# laser_show_adc_uart.net
KiCad netlist of a schematic drawn in Altium Designer
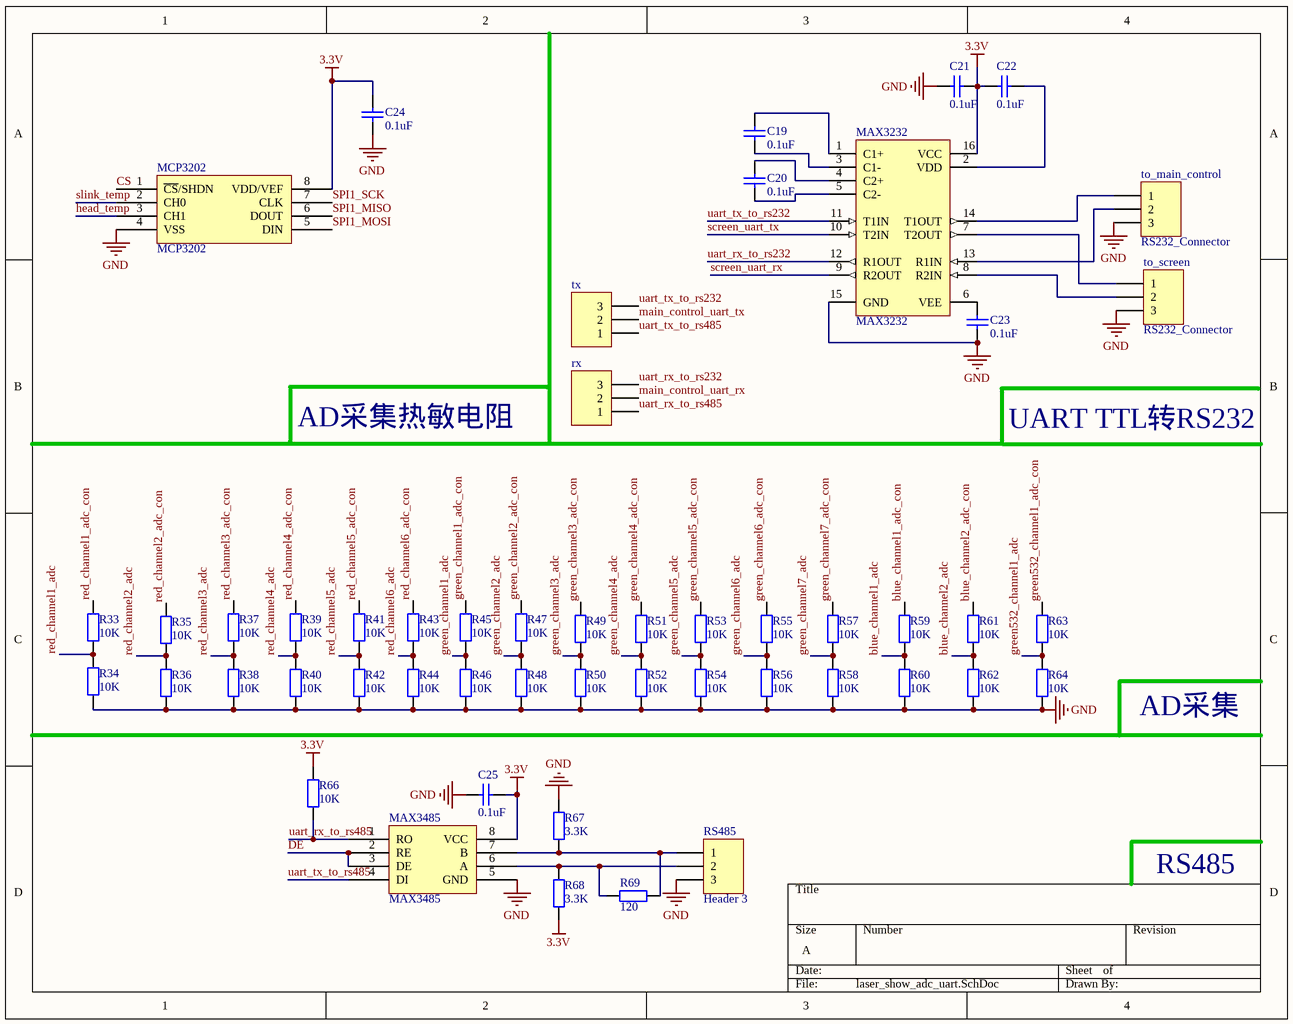
[diagram p0: laser_show_adc_uart.SchDoc]

(export (version "E")
  (design (tool "Eeschema 10.0.6"))
  (components
    (comp (ref "C19")
      (value "0.1uF")
      (footprint "0603C")
      (description "capacitance")
      (libsource (lib "RobotSCHLibrary") (part "CAP"))
    )
    (comp (ref "C20")
      (value "0.1uF")
      (footprint "0603C")
      (description "capacitance")
      (libsource (lib "RobotSCHLibrary") (part "CAP"))
    )
    (comp (ref "C21")
      (value "0.1uF")
      (footprint "0603C")
      (description "capacitance")
      (libsource (lib "RobotSCHLibrary") (part "CAP"))
    )
    (comp (ref "C22")
      (value "0.1uF")
      (footprint "0603C")
      (description "capacitance")
      (libsource (lib "RobotSCHLibrary") (part "CAP"))
    )
    (comp (ref "C23")
      (value "0.1uF")
      (footprint "0603C")
      (description "capacitance")
      (libsource (lib "RobotSCHLibrary") (part "CAP"))
    )
    (comp (ref "C24")
      (value "0.1uF")
      (footprint "0603C")
      (description "capacitance")
      (libsource (lib "RobotSCHLibrary") (part "CAP"))
    )
    (comp (ref "C25")
      (value "0.1uF")
      (footprint "0603C")
      (description "capacitance")
      (libsource (lib "RobotSCHLibrary") (part "CAP"))
    )
    (comp (ref "MAX3232")
      (value "MAX3232")
      (footprint "SO-16")
      (description "+5V Powered, Multi-Channel RS-232 Driver/Receiver")
      (fields (field (name "PUBLISHER") "Altium Limited"))
      (libsource (lib "Fszhang") (part "MAX232"))
    )
    (comp (ref "MAX3485")
      (value "MAX3485")
      (footprint "so-8")
      (libsource (lib "RobotSCHLibrary") (part "MAX485"))
    )
    (comp (ref "MCP3202")
      (value "MCP3202")
      (footprint "SOIC8N_L")
      (libsource (lib "RobotSCHLibrary") (part "MCP3202"))
    )
    (comp (ref "R33")
      (value "10K")
      (footprint "0805R")
      (description "resistor")
      (libsource (lib "RobotSCHLibrary") (part "RES"))
    )
    (comp (ref "R34")
      (value "10K")
      (footprint "0805R")
      (description "resistor")
      (libsource (lib "RobotSCHLibrary") (part "RES"))
    )
    (comp (ref "R35")
      (value "10K")
      (footprint "0805R")
      (description "resistor")
      (libsource (lib "RobotSCHLibrary") (part "RES"))
    )
    (comp (ref "R36")
      (value "10K")
      (footprint "0805R")
      (description "resistor")
      (libsource (lib "RobotSCHLibrary") (part "RES"))
    )
    (comp (ref "R37")
      (value "10K")
      (footprint "0805R")
      (description "resistor")
      (libsource (lib "RobotSCHLibrary") (part "RES"))
    )
    (comp (ref "R38")
      (value "10K")
      (footprint "0805R")
      (description "resistor")
      (libsource (lib "RobotSCHLibrary") (part "RES"))
    )
    (comp (ref "R39")
      (value "10K")
      (footprint "0805R")
      (description "resistor")
      (libsource (lib "RobotSCHLibrary") (part "RES"))
    )
    (comp (ref "R40")
      (value "10K")
      (footprint "0805R")
      (description "resistor")
      (libsource (lib "RobotSCHLibrary") (part "RES"))
    )
    (comp (ref "R41")
      (value "10K")
      (footprint "0805R")
      (description "resistor")
      (libsource (lib "RobotSCHLibrary") (part "RES"))
    )
    (comp (ref "R42")
      (value "10K")
      (footprint "0805R")
      (description "resistor")
      (libsource (lib "RobotSCHLibrary") (part "RES"))
    )
    (comp (ref "R43")
      (value "10K")
      (footprint "0805R")
      (description "resistor")
      (libsource (lib "RobotSCHLibrary") (part "RES"))
    )
    (comp (ref "R44")
      (value "10K")
      (footprint "0805R")
      (description "resistor")
      (libsource (lib "RobotSCHLibrary") (part "RES"))
    )
    (comp (ref "R45")
      (value "10K")
      (footprint "0805R")
      (description "resistor")
      (libsource (lib "RobotSCHLibrary") (part "RES"))
    )
    (comp (ref "R46")
      (value "10K")
      (footprint "0805R")
      (description "resistor")
      (libsource (lib "RobotSCHLibrary") (part "RES"))
    )
    (comp (ref "R47")
      (value "10K")
      (footprint "0805R")
      (description "resistor")
      (libsource (lib "RobotSCHLibrary") (part "RES"))
    )
    (comp (ref "R48")
      (value "10K")
      (footprint "0805R")
      (description "resistor")
      (libsource (lib "RobotSCHLibrary") (part "RES"))
    )
    (comp (ref "R49")
      (value "10K")
      (footprint "0805R")
      (description "resistor")
      (libsource (lib "RobotSCHLibrary") (part "RES"))
    )
    (comp (ref "R50")
      (value "10K")
      (footprint "0805R")
      (description "resistor")
      (libsource (lib "RobotSCHLibrary") (part "RES"))
    )
    (comp (ref "R51")
      (value "10K")
      (footprint "0805R")
      (description "resistor")
      (libsource (lib "RobotSCHLibrary") (part "RES"))
    )
    (comp (ref "R52")
      (value "10K")
      (footprint "0805R")
      (description "resistor")
      (libsource (lib "RobotSCHLibrary") (part "RES"))
    )
    (comp (ref "R53")
      (value "10K")
      (footprint "0805R")
      (description "resistor")
      (libsource (lib "RobotSCHLibrary") (part "RES"))
    )
    (comp (ref "R54")
      (value "10K")
      (footprint "0805R")
      (description "resistor")
      (libsource (lib "RobotSCHLibrary") (part "RES"))
    )
    (comp (ref "R55")
      (value "10K")
      (footprint "0805R")
      (description "resistor")
      (libsource (lib "RobotSCHLibrary") (part "RES"))
    )
    (comp (ref "R56")
      (value "10K")
      (footprint "0805R")
      (description "resistor")
      (libsource (lib "RobotSCHLibrary") (part "RES"))
    )
    (comp (ref "R57")
      (value "10K")
      (footprint "0805R")
      (description "resistor")
      (libsource (lib "RobotSCHLibrary") (part "RES"))
    )
    (comp (ref "R58")
      (value "10K")
      (footprint "0805R")
      (description "resistor")
      (libsource (lib "RobotSCHLibrary") (part "RES"))
    )
    (comp (ref "R59")
      (value "10K")
      (footprint "0805R")
      (description "resistor")
      (libsource (lib "RobotSCHLibrary") (part "RES"))
    )
    (comp (ref "R60")
      (value "10K")
      (footprint "0805R")
      (description "resistor")
      (libsource (lib "RobotSCHLibrary") (part "RES"))
    )
    (comp (ref "R61")
      (value "10K")
      (footprint "0805R")
      (description "resistor")
      (libsource (lib "RobotSCHLibrary") (part "RES"))
    )
    (comp (ref "R62")
      (value "10K")
      (footprint "0805R")
      (description "resistor")
      (libsource (lib "RobotSCHLibrary") (part "RES"))
    )
    (comp (ref "R63")
      (value "10K")
      (footprint "0805R")
      (description "resistor")
      (libsource (lib "RobotSCHLibrary") (part "RES"))
    )
    (comp (ref "R64")
      (value "10K")
      (footprint "0805R")
      (description "resistor")
      (libsource (lib "RobotSCHLibrary") (part "RES"))
    )
    (comp (ref "R66")
      (value "10K")
      (footprint "0603R")
      (description "resistor")
      (libsource (lib "RobotSCHLibrary") (part "RES"))
    )
    (comp (ref "R67")
      (value "3.3K")
      (footprint "0603R")
      (description "resistor")
      (libsource (lib "RobotSCHLibrary") (part "RES"))
    )
    (comp (ref "R68")
      (value "3.3K")
      (footprint "0603R")
      (description "resistor")
      (libsource (lib "RobotSCHLibrary") (part "RES"))
    )
    (comp (ref "R69")
      (value "120")
      (footprint "0603R")
      (description "resistor")
      (libsource (lib "") (part "RES_1"))
    )
    (comp (ref "RS485")
      (value "Header 3")
      (footprint "XH2.54_3P_Vertical")
      (description "Header, 3-Pin")
      (fields (field (name "PUBLISHER") "Altium Limited"))
      (libsource (lib "Miscellaneous Connectors") (part "Header 3"))
    )
    (comp (ref "rx")
      (value "main")
      (footprint "HDR1X3")
      (description "Header, 3-Pin")
      (fields (field (name "PUBLISHER") "Altium Limited"))
      (libsource (lib "") (part "Header 3_1"))
    )
    (comp (ref "to_main_control")
      (value "RS232_Connector")
      (footprint "XH2.54_3P_Vertical")
      (description "Header, 3-Pin")
      (fields (field (name "PUBLISHER") "Altium Limited"))
      (libsource (lib "Miscellaneous Connectors") (part "Header 3"))
    )
    (comp (ref "to_screen")
      (value "RS232_Connector")
      (footprint "XH2.54_3P_Vertical")
      (description "Header, 3-Pin")
      (fields (field (name "PUBLISHER") "Altium Limited"))
      (libsource (lib "Miscellaneous Connectors") (part "Header 3"))
    )
    (comp (ref "tx")
      (value "RS232")
      (footprint "HDR1X3")
      (description "Header, 3-Pin")
      (fields (field (name "PUBLISHER") "Altium Limited"))
      (libsource (lib "") (part "Header 3_1"))
    )
  )
  (nets
    (net (code "1") (name "/CS") (class "Default")
      (node (ref "MCP3202") (pin "1") (pinfunction "~{CS}/SHDN_1") (pintype "passive"))
    )
    (net (code "2") (name "/DE") (class "Default")
      (node (ref "MAX3485") (pin "2") (pinfunction "RE_2") (pintype "passive"))
      (node (ref "MAX3485") (pin "3") (pinfunction "DE_3") (pintype "passive"))
    )
    (net (code "3") (name "/SPI1_MISO") (class "Default")
      (node (ref "MCP3202") (pin "6") (pinfunction "DOUT_6") (pintype "passive"))
    )
    (net (code "4") (name "/SPI1_MOSI") (class "Default")
      (node (ref "MCP3202") (pin "5") (pinfunction "DIN_5") (pintype "passive"))
    )
    (net (code "5") (name "/SPI1_SCK") (class "Default")
      (node (ref "MCP3202") (pin "7") (pinfunction "CLK_7") (pintype "passive"))
    )
    (net (code "6") (name "/blue_channel1_adc") (class "Default")
      (node (ref "R59") (pin "1") (pinfunction "1_1") (pintype "passive"))
      (node (ref "R60") (pin "2") (pinfunction "2_2") (pintype "passive"))
    )
    (net (code "7") (name "/blue_channel1_adc_con") (class "Default")
      (node (ref "R59") (pin "2") (pinfunction "2_2") (pintype "passive"))
    )
    (net (code "8") (name "/blue_channel2_adc") (class "Default")
      (node (ref "R61") (pin "1") (pinfunction "1_1") (pintype "passive"))
      (node (ref "R62") (pin "2") (pinfunction "2_2") (pintype "passive"))
    )
    (net (code "9") (name "/blue_channel2_adc_con") (class "Default")
      (node (ref "R61") (pin "2") (pinfunction "2_2") (pintype "passive"))
    )
    (net (code "10") (name "/green532_channel1_adc") (class "Default")
      (node (ref "R63") (pin "1") (pinfunction "1_1") (pintype "passive"))
      (node (ref "R64") (pin "2") (pinfunction "2_2") (pintype "passive"))
    )
    (net (code "11") (name "/green532_channel1_adc_con") (class "Default")
      (node (ref "R63") (pin "2") (pinfunction "2_2") (pintype "passive"))
    )
    (net (code "12") (name "/green_channel1_adc") (class "Default")
      (node (ref "R45") (pin "1") (pinfunction "1_1") (pintype "passive"))
      (node (ref "R46") (pin "2") (pinfunction "2_2") (pintype "passive"))
    )
    (net (code "13") (name "/green_channel1_adc_con") (class "Default")
      (node (ref "R45") (pin "2") (pinfunction "2_2") (pintype "passive"))
    )
    (net (code "14") (name "/green_channel2_adc") (class "Default")
      (node (ref "R47") (pin "1") (pinfunction "1_1") (pintype "passive"))
      (node (ref "R48") (pin "2") (pinfunction "2_2") (pintype "passive"))
    )
    (net (code "15") (name "/green_channel2_adc_con") (class "Default")
      (node (ref "R47") (pin "2") (pinfunction "2_2") (pintype "passive"))
    )
    (net (code "16") (name "/green_channel3_adc") (class "Default")
      (node (ref "R49") (pin "1") (pinfunction "1_1") (pintype "passive"))
      (node (ref "R50") (pin "2") (pinfunction "2_2") (pintype "passive"))
    )
    (net (code "17") (name "/green_channel3_adc_con") (class "Default")
      (node (ref "R49") (pin "2") (pinfunction "2_2") (pintype "passive"))
    )
    (net (code "18") (name "/green_channel4_adc") (class "Default")
      (node (ref "R51") (pin "1") (pinfunction "1_1") (pintype "passive"))
      (node (ref "R52") (pin "2") (pinfunction "2_2") (pintype "passive"))
    )
    (net (code "19") (name "/green_channel4_adc_con") (class "Default")
      (node (ref "R51") (pin "2") (pinfunction "2_2") (pintype "passive"))
    )
    (net (code "20") (name "/green_channel5_adc") (class "Default")
      (node (ref "R53") (pin "1") (pinfunction "1_1") (pintype "passive"))
      (node (ref "R54") (pin "2") (pinfunction "2_2") (pintype "passive"))
    )
    (net (code "21") (name "/green_channel5_adc_con") (class "Default")
      (node (ref "R53") (pin "2") (pinfunction "2_2") (pintype "passive"))
    )
    (net (code "22") (name "/green_channel6_adc") (class "Default")
      (node (ref "R55") (pin "1") (pinfunction "1_1") (pintype "passive"))
      (node (ref "R56") (pin "2") (pinfunction "2_2") (pintype "passive"))
    )
    (net (code "23") (name "/green_channel6_adc_con") (class "Default")
      (node (ref "R55") (pin "2") (pinfunction "2_2") (pintype "passive"))
    )
    (net (code "24") (name "/green_channel7_adc") (class "Default")
      (node (ref "R57") (pin "1") (pinfunction "1_1") (pintype "passive"))
      (node (ref "R58") (pin "2") (pinfunction "2_2") (pintype "passive"))
    )
    (net (code "25") (name "/green_channel7_adc_con") (class "Default")
      (node (ref "R57") (pin "2") (pinfunction "2_2") (pintype "passive"))
    )
    (net (code "26") (name "/head_temp") (class "Default")
      (node (ref "MCP3202") (pin "3") (pinfunction "CH1_3") (pintype "passive"))
    )
    (net (code "27") (name "/main_control_uart_rx") (class "Default")
      (node (ref "rx") (pin "2") (pinfunction "2_2") (pintype "passive"))
    )
    (net (code "28") (name "/main_control_uart_tx") (class "Default")
      (node (ref "tx") (pin "2") (pinfunction "2_2") (pintype "passive"))
    )
    (net (code "29") (name "/red_channel1_adc") (class "Default")
      (node (ref "R33") (pin "1") (pinfunction "1_1") (pintype "passive"))
      (node (ref "R34") (pin "2") (pinfunction "2_2") (pintype "passive"))
    )
    (net (code "30") (name "/red_channel1_adc_con") (class "Default")
      (node (ref "R33") (pin "2") (pinfunction "2_2") (pintype "passive"))
    )
    (net (code "31") (name "/red_channel2_adc") (class "Default")
      (node (ref "R35") (pin "1") (pinfunction "1_1") (pintype "passive"))
      (node (ref "R36") (pin "2") (pinfunction "2_2") (pintype "passive"))
    )
    (net (code "32") (name "/red_channel2_adc_con") (class "Default")
      (node (ref "R35") (pin "2") (pinfunction "2_2") (pintype "passive"))
    )
    (net (code "33") (name "/red_channel3_adc") (class "Default")
      (node (ref "R37") (pin "1") (pinfunction "1_1") (pintype "passive"))
      (node (ref "R38") (pin "2") (pinfunction "2_2") (pintype "passive"))
    )
    (net (code "34") (name "/red_channel3_adc_con") (class "Default")
      (node (ref "R37") (pin "2") (pinfunction "2_2") (pintype "passive"))
    )
    (net (code "35") (name "/red_channel4_adc") (class "Default")
      (node (ref "R39") (pin "1") (pinfunction "1_1") (pintype "passive"))
      (node (ref "R40") (pin "2") (pinfunction "2_2") (pintype "passive"))
    )
    (net (code "36") (name "/red_channel4_adc_con") (class "Default")
      (node (ref "R39") (pin "2") (pinfunction "2_2") (pintype "passive"))
    )
    (net (code "37") (name "/red_channel5_adc") (class "Default")
      (node (ref "R41") (pin "1") (pinfunction "1_1") (pintype "passive"))
      (node (ref "R42") (pin "2") (pinfunction "2_2") (pintype "passive"))
    )
    (net (code "38") (name "/red_channel5_adc_con") (class "Default")
      (node (ref "R41") (pin "2") (pinfunction "2_2") (pintype "passive"))
    )
    (net (code "39") (name "/red_channel6_adc") (class "Default")
      (node (ref "R43") (pin "1") (pinfunction "1_1") (pintype "passive"))
      (node (ref "R44") (pin "2") (pinfunction "2_2") (pintype "passive"))
    )
    (net (code "40") (name "/red_channel6_adc_con") (class "Default")
      (node (ref "R43") (pin "2") (pinfunction "2_2") (pintype "passive"))
    )
    (net (code "41") (name "/screen_uart_rx") (class "Default")
      (node (ref "MAX3232") (pin "9") (pinfunction "R2OUT_9") (pintype "output"))
    )
    (net (code "42") (name "/screen_uart_tx") (class "Default")
      (node (ref "MAX3232") (pin "10") (pinfunction "T2IN_10") (pintype "input"))
    )
    (net (code "43") (name "/slink_temp") (class "Default")
      (node (ref "MCP3202") (pin "2") (pinfunction "CH0_2") (pintype "passive"))
    )
    (net (code "44") (name "/uart_rx_to_rs232") (class "Default")
      (node (ref "MAX3232") (pin "12") (pinfunction "R1OUT_12") (pintype "output"))
      (node (ref "rx") (pin "3") (pinfunction "3_3") (pintype "passive"))
    )
    (net (code "45") (name "/uart_rx_to_rs485") (class "Default")
      (node (ref "MAX3485") (pin "1") (pinfunction "RO_1") (pintype "passive"))
      (node (ref "R66") (pin "1") (pinfunction "1_1") (pintype "passive"))
      (node (ref "rx") (pin "1") (pinfunction "1_1") (pintype "passive"))
    )
    (net (code "46") (name "/uart_tx_to_rs232") (class "Default")
      (node (ref "MAX3232") (pin "11") (pinfunction "T1IN_11") (pintype "input"))
      (node (ref "tx") (pin "3") (pinfunction "3_3") (pintype "passive"))
    )
    (net (code "47") (name "/uart_tx_to_rs485") (class "Default")
      (node (ref "MAX3485") (pin "4") (pinfunction "DI_4") (pintype "passive"))
      (node (ref "tx") (pin "1") (pinfunction "1_1") (pintype "passive"))
    )
    (net (code "48") (name "3.3V") (class "Default")
      (node (ref "C21") (pin "1") (pinfunction "1_1") (pintype "passive"))
      (node (ref "C22") (pin "2") (pinfunction "2_2") (pintype "passive"))
      (node (ref "C24") (pin "2") (pinfunction "2_2") (pintype "passive"))
      (node (ref "C25") (pin "1") (pinfunction "1_1") (pintype "passive"))
      (node (ref "MAX3232") (pin "16") (pinfunction "VCC_16") (pintype "power_in"))
      (node (ref "MAX3485") (pin "8") (pinfunction "VCC_8") (pintype "passive"))
      (node (ref "MCP3202") (pin "8") (pinfunction "VDD/VEF_8") (pintype "passive"))
      (node (ref "R66") (pin "2") (pinfunction "2_2") (pintype "passive"))
      (node (ref "R68") (pin "1") (pinfunction "1_1") (pintype "passive"))
    )
    (net (code "49") (name "GND") (class "Default")
      (node (ref "C21") (pin "2") (pinfunction "2_2") (pintype "passive"))
      (node (ref "C23") (pin "1") (pinfunction "1_1") (pintype "passive"))
      (node (ref "C24") (pin "1") (pinfunction "1_1") (pintype "passive"))
      (node (ref "C25") (pin "2") (pinfunction "2_2") (pintype "passive"))
      (node (ref "MAX3232") (pin "15") (pinfunction "GND_15") (pintype "power_in"))
      (node (ref "MAX3485") (pin "5") (pinfunction "GND_5") (pintype "passive"))
      (node (ref "MCP3202") (pin "4") (pinfunction "VSS_4") (pintype "passive"))
      (node (ref "R34") (pin "1") (pinfunction "1_1") (pintype "passive"))
      (node (ref "R36") (pin "1") (pinfunction "1_1") (pintype "passive"))
      (node (ref "R38") (pin "1") (pinfunction "1_1") (pintype "passive"))
      (node (ref "R40") (pin "1") (pinfunction "1_1") (pintype "passive"))
      (node (ref "R42") (pin "1") (pinfunction "1_1") (pintype "passive"))
      (node (ref "R44") (pin "1") (pinfunction "1_1") (pintype "passive"))
      (node (ref "R46") (pin "1") (pinfunction "1_1") (pintype "passive"))
      (node (ref "R48") (pin "1") (pinfunction "1_1") (pintype "passive"))
      (node (ref "R50") (pin "1") (pinfunction "1_1") (pintype "passive"))
      (node (ref "R52") (pin "1") (pinfunction "1_1") (pintype "passive"))
      (node (ref "R54") (pin "1") (pinfunction "1_1") (pintype "passive"))
      (node (ref "R56") (pin "1") (pinfunction "1_1") (pintype "passive"))
      (node (ref "R58") (pin "1") (pinfunction "1_1") (pintype "passive"))
      (node (ref "R60") (pin "1") (pinfunction "1_1") (pintype "passive"))
      (node (ref "R62") (pin "1") (pinfunction "1_1") (pintype "passive"))
      (node (ref "R64") (pin "1") (pinfunction "1_1") (pintype "passive"))
      (node (ref "R67") (pin "2") (pinfunction "2_2") (pintype "passive"))
      (node (ref "RS485") (pin "3") (pinfunction "3_3") (pintype "passive"))
      (node (ref "to_main_control") (pin "3") (pinfunction "3_3") (pintype "passive"))
      (node (ref "to_screen") (pin "3") (pinfunction "3_3") (pintype "passive"))
    )
    (net (code "50") (name "Net-(MAX3232-C1+)") (class "Default")
      (node (ref "C19") (pin "2") (pinfunction "2_2") (pintype "passive"))
      (node (ref "MAX3232") (pin "1") (pinfunction "C1+_1") (pintype "passive"))
    )
    (net (code "51") (name "Net-(MAX3232-C1-)") (class "Default")
      (node (ref "C19") (pin "1") (pinfunction "1_1") (pintype "passive"))
      (node (ref "MAX3232") (pin "3") (pinfunction "C1-_3") (pintype "passive"))
    )
    (net (code "52") (name "Net-(MAX3232-C2+)") (class "Default")
      (node (ref "C20") (pin "2") (pinfunction "2_2") (pintype "passive"))
      (node (ref "MAX3232") (pin "4") (pinfunction "C2+_4") (pintype "passive"))
    )
    (net (code "53") (name "Net-(MAX3232-C2-)") (class "Default")
      (node (ref "C20") (pin "1") (pinfunction "1_1") (pintype "passive"))
      (node (ref "MAX3232") (pin "5") (pinfunction "C2-_5") (pintype "passive"))
    )
    (net (code "54") (name "Net-(MAX3232-R1IN)") (class "Default")
      (node (ref "MAX3232") (pin "13") (pinfunction "R1IN_13") (pintype "input"))
      (node (ref "to_main_control") (pin "2") (pinfunction "2_2") (pintype "passive"))
    )
    (net (code "55") (name "Net-(MAX3232-R2IN)") (class "Default")
      (node (ref "MAX3232") (pin "8") (pinfunction "R2IN_8") (pintype "input"))
      (node (ref "to_screen") (pin "2") (pinfunction "2_2") (pintype "passive"))
    )
    (net (code "56") (name "Net-(MAX3232-T1OUT)") (class "Default")
      (node (ref "MAX3232") (pin "14") (pinfunction "T1OUT_14") (pintype "output"))
      (node (ref "to_main_control") (pin "1") (pinfunction "1_1") (pintype "passive"))
    )
    (net (code "57") (name "Net-(MAX3232-T2OUT)") (class "Default")
      (node (ref "MAX3232") (pin "7") (pinfunction "T2OUT_7") (pintype "output"))
      (node (ref "to_screen") (pin "1") (pinfunction "1_1") (pintype "passive"))
    )
    (net (code "58") (name "Net-(MAX3232-VDD)") (class "Default")
      (node (ref "C22") (pin "1") (pinfunction "1_1") (pintype "passive"))
      (node (ref "MAX3232") (pin "2") (pinfunction "VDD_2") (pintype "power_in"))
    )
    (net (code "59") (name "Net-(MAX3232-VEE)") (class "Default")
      (node (ref "C23") (pin "2") (pinfunction "2_2") (pintype "passive"))
      (node (ref "MAX3232") (pin "6") (pinfunction "VEE_6") (pintype "power_in"))
    )
    (net (code "60") (name "Net-(MAX3485-A)") (class "Default")
      (node (ref "MAX3485") (pin "6") (pinfunction "A_6") (pintype "passive"))
      (node (ref "R68") (pin "2") (pinfunction "2_2") (pintype "passive"))
      (node (ref "R69") (pin "2") (pinfunction "2_2") (pintype "passive"))
      (node (ref "RS485") (pin "2") (pinfunction "2_2") (pintype "passive"))
    )
    (net (code "61") (name "Net-(MAX3485-B)") (class "Default")
      (node (ref "MAX3485") (pin "7") (pinfunction "B_7") (pintype "passive"))
      (node (ref "R67") (pin "1") (pinfunction "1_1") (pintype "passive"))
      (node (ref "R69") (pin "1") (pinfunction "1_1") (pintype "passive"))
      (node (ref "RS485") (pin "1") (pinfunction "1_1") (pintype "passive"))
    )
  )
)
